# furby_connector_01.net
KiCad netlist of a schematic drawn in EAGLE
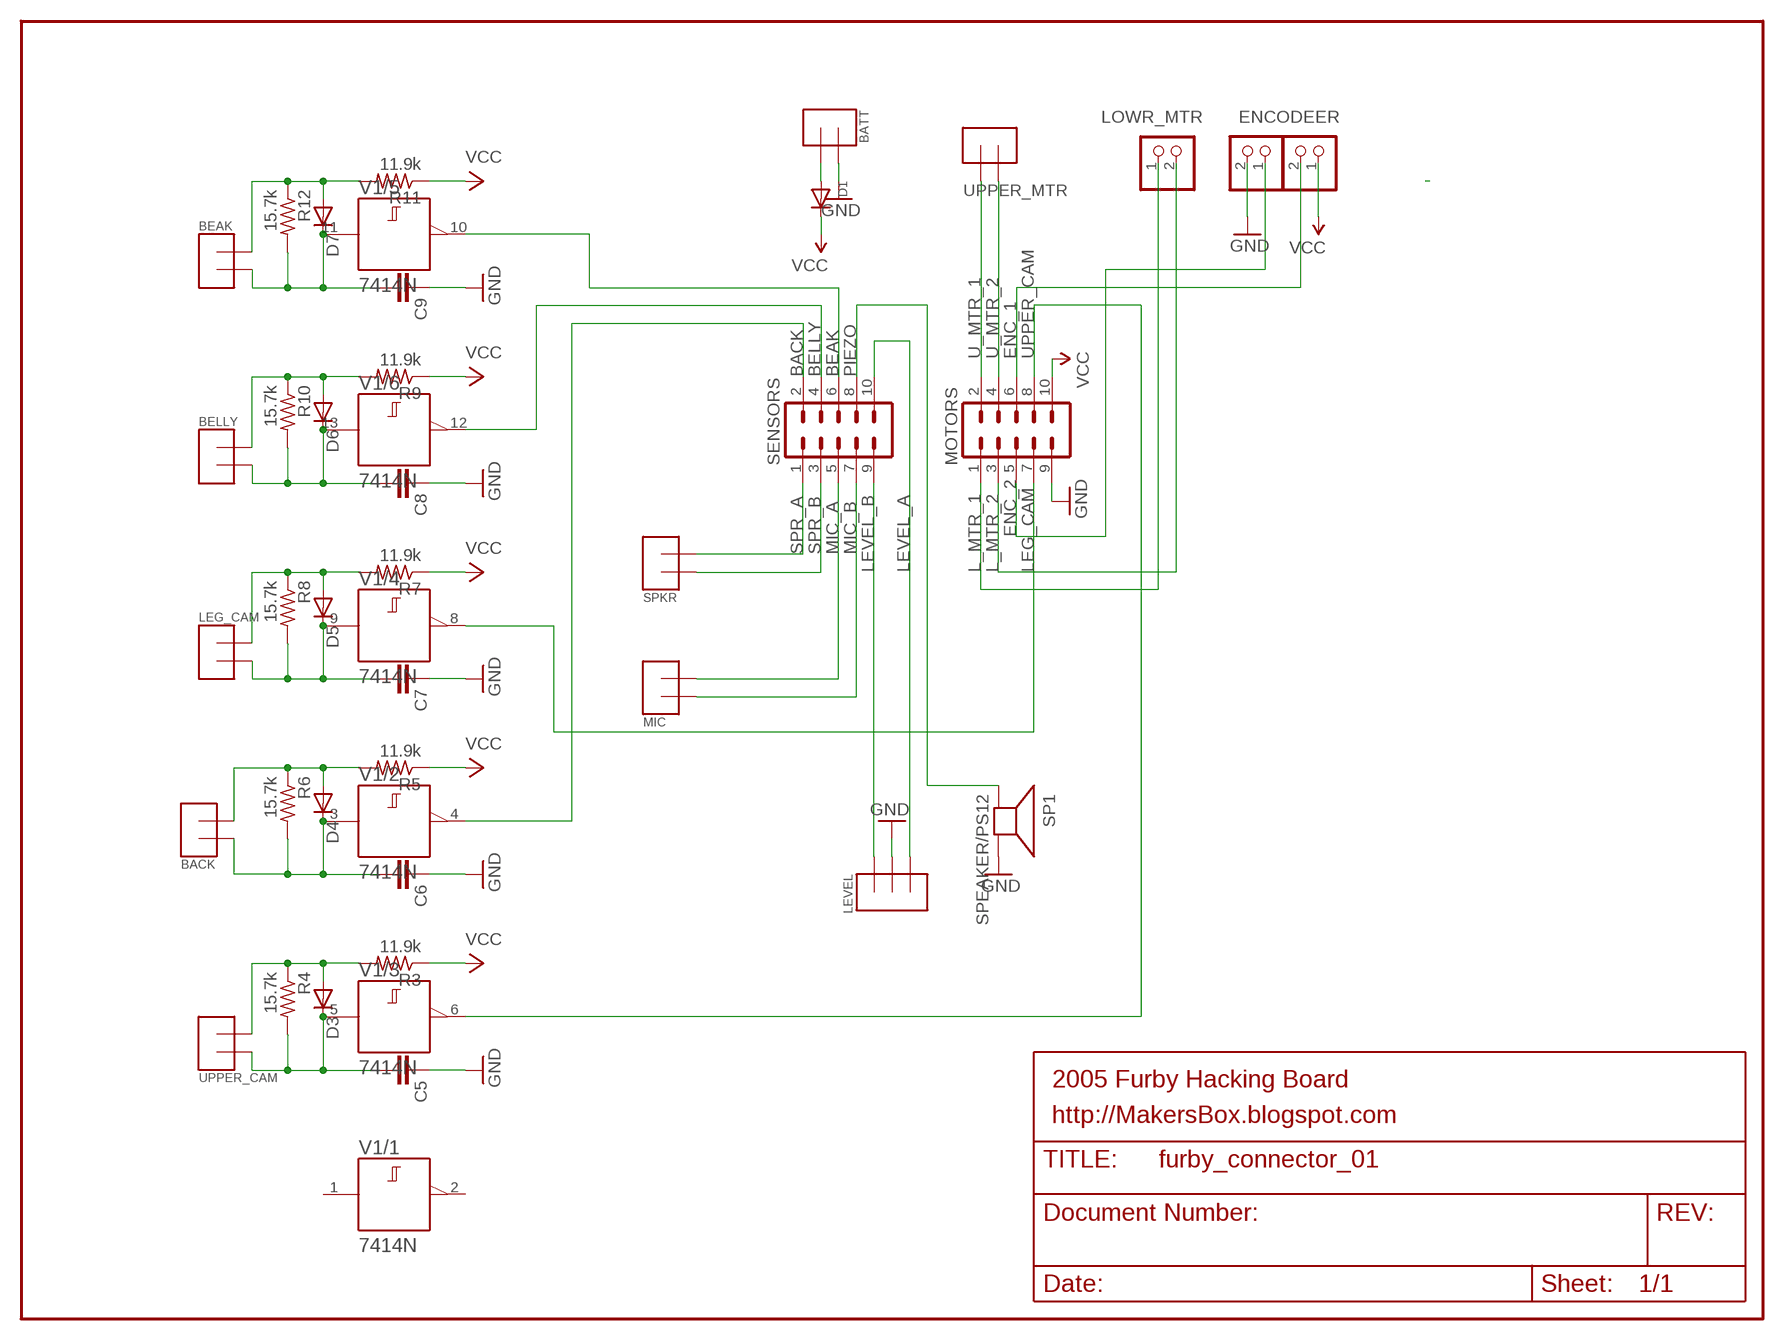
[diagram p0: schematic, sheet 1]

(export (version "E")
  (design (tool "Eeschema 10.0.6"))
  (components
    (comp (ref "BACK")
      (value "TERMINAL2")
      (footprint "eagle-import:TERMINAL_2")
      (libsource (lib "eagle-import") (part "TERMINAL2"))
    )
    (comp (ref "BATT")
      (value "TERMINAL2")
      (footprint "eagle-import:TERMINAL_2")
      (libsource (lib "eagle-import") (part "TERMINAL2"))
    )
    (comp (ref "BEAK")
      (value "TERMINAL2")
      (footprint "eagle-import:TERMINAL_2")
      (libsource (lib "eagle-import") (part "TERMINAL2"))
    )
    (comp (ref "BELLY")
      (value "TERMINAL2")
      (footprint "eagle-import:TERMINAL_2")
      (libsource (lib "eagle-import") (part "TERMINAL2"))
    )
    (comp (ref "C5")
      (value "CAPPTH")
      (footprint "eagle-import:CAP-PTH-SMALL")
      (libsource (lib "eagle-import") (part "CAPPTH"))
    )
    (comp (ref "C6")
      (value "CAPPTH")
      (footprint "eagle-import:CAP-PTH-SMALL")
      (libsource (lib "eagle-import") (part "CAPPTH"))
    )
    (comp (ref "C7")
      (value "CAPPTH")
      (footprint "eagle-import:CAP-PTH-SMALL")
      (libsource (lib "eagle-import") (part "CAPPTH"))
    )
    (comp (ref "C8")
      (value "CAPPTH")
      (footprint "eagle-import:CAP-PTH-SMALL")
      (libsource (lib "eagle-import") (part "CAPPTH"))
    )
    (comp (ref "C9")
      (value "CAPPTH")
      (footprint "eagle-import:CAP-PTH-SMALL")
      (libsource (lib "eagle-import") (part "CAPPTH"))
    )
    (comp (ref "D1")
      (value "DIODEDO-1N4148")
      (footprint "eagle-import:DO-1N4148")
      (libsource (lib "eagle-import") (part "DIODEDO-1N4148"))
    )
    (comp (ref "D3")
      (value "DIODE-D-2.5")
      (footprint "eagle-import:D-2.5")
      (libsource (lib "eagle-import") (part "DIODE-D-2.5"))
    )
    (comp (ref "D4")
      (value "DIODE-D-2.5")
      (footprint "eagle-import:D-2.5")
      (libsource (lib "eagle-import") (part "DIODE-D-2.5"))
    )
    (comp (ref "D5")
      (value "DIODE-D-2.5")
      (footprint "eagle-import:D-2.5")
      (libsource (lib "eagle-import") (part "DIODE-D-2.5"))
    )
    (comp (ref "D6")
      (value "DIODE-D-2.5")
      (footprint "eagle-import:D-2.5")
      (libsource (lib "eagle-import") (part "DIODE-D-2.5"))
    )
    (comp (ref "D7")
      (value "DIODE-D-2.5")
      (footprint "eagle-import:D-2.5")
      (libsource (lib "eagle-import") (part "DIODE-D-2.5"))
    )
    (comp (ref "ENCODE2")
      (value "JST_2PIN-THM")
      (footprint "eagle-import:JST-PH-2-THM")
      (libsource (lib "eagle-import") (part "JST_2PIN-THM"))
    )
    (comp (ref "ENCODEER")
      (value "JST_2PIN-THM")
      (footprint "eagle-import:JST-PH-2-THM")
      (libsource (lib "eagle-import") (part "JST_2PIN-THM"))
    )
    (comp (ref "LEG_CAM")
      (value "TERMINAL2")
      (footprint "eagle-import:TERMINAL_2")
      (libsource (lib "eagle-import") (part "TERMINAL2"))
    )
    (comp (ref "LEVEL")
      (value "TERMINAL")
      (footprint "eagle-import:TERMINAL_3")
      (libsource (lib "eagle-import") (part "TERMINAL"))
    )
    (comp (ref "LOWR_MTR")
      (value "JST_2PIN-THM")
      (footprint "eagle-import:JST-PH-2-THM")
      (libsource (lib "eagle-import") (part "JST_2PIN-THM"))
    )
    (comp (ref "MIC")
      (value "TERMINAL2")
      (footprint "eagle-import:TERMINAL_2")
      (libsource (lib "eagle-import") (part "TERMINAL2"))
    )
    (comp (ref "MOTORS")
      (value "M05X2SHD")
      (footprint "eagle-import:2X5-SHROUDED")
      (libsource (lib "eagle-import") (part "M05X2SHD"))
    )
    (comp (ref "R3")
      (value "11.9k")
      (footprint "eagle-import:0204V")
      (libsource (lib "eagle-import") (part "R-US_0204/2V"))
    )
    (comp (ref "R4")
      (value "15.7k")
      (footprint "eagle-import:0204V")
      (libsource (lib "eagle-import") (part "R-US_0204/2V"))
    )
    (comp (ref "R5")
      (value "11.9k")
      (footprint "eagle-import:0204V")
      (libsource (lib "eagle-import") (part "R-US_0204/2V"))
    )
    (comp (ref "R6")
      (value "15.7k")
      (footprint "eagle-import:0204V")
      (libsource (lib "eagle-import") (part "R-US_0204/2V"))
    )
    (comp (ref "R7")
      (value "11.9k")
      (footprint "eagle-import:0204V")
      (libsource (lib "eagle-import") (part "R-US_0204/2V"))
    )
    (comp (ref "R8")
      (value "15.7k")
      (footprint "eagle-import:0204V")
      (libsource (lib "eagle-import") (part "R-US_0204/2V"))
    )
    (comp (ref "R9")
      (value "11.9k")
      (footprint "eagle-import:0204V")
      (libsource (lib "eagle-import") (part "R-US_0204/2V"))
    )
    (comp (ref "R10")
      (value "15.7k")
      (footprint "eagle-import:0204V")
      (libsource (lib "eagle-import") (part "R-US_0204/2V"))
    )
    (comp (ref "R11")
      (value "11.9k")
      (footprint "eagle-import:0204V")
      (libsource (lib "eagle-import") (part "R-US_0204/2V"))
    )
    (comp (ref "R12")
      (value "15.7k")
      (footprint "eagle-import:0204V")
      (libsource (lib "eagle-import") (part "R-US_0204/2V"))
    )
    (comp (ref "SENSORS")
      (value "M05X2SHD")
      (footprint "eagle-import:2X5-SHROUDED")
      (libsource (lib "eagle-import") (part "M05X2SHD"))
    )
    (comp (ref "SP1")
      (value "SPEAKER/PS12")
      (footprint "eagle-import:PS12")
      (libsource (lib "eagle-import") (part "SPEAKER/PS12"))
    )
    (comp (ref "SPKR")
      (value "TERMINAL2")
      (footprint "eagle-import:TERMINAL_2")
      (libsource (lib "eagle-import") (part "TERMINAL2"))
    )
    (comp (ref "UPPER_CAM")
      (value "TERMINAL2")
      (footprint "eagle-import:TERMINAL_2")
      (libsource (lib "eagle-import") (part "TERMINAL2"))
    )
    (comp (ref "UPPER_MTR")
      (value "TERMINAL2")
      (footprint "eagle-import:TERMINAL_2")
      (libsource (lib "eagle-import") (part "TERMINAL2"))
    )
    (comp (ref "V1")
      (value "7414N")
      (footprint "eagle-import:DIL14")
      (libsource (lib "eagle-import") (part "7414N"))
    )
  )
  (nets
    (net (code "1") (name "/BACK") (class "Default")
      (node (ref "SENSORS") (pin "2") (pinfunction "2_2") (pintype "passive"))
      (node (ref "V1") (pin "4") (pinfunction "Y_4") (pintype "output"))
    )
    (net (code "2") (name "/BEAK") (class "Default")
      (node (ref "SENSORS") (pin "6") (pinfunction "6_6") (pintype "passive"))
      (node (ref "V1") (pin "10") (pinfunction "Y_10") (pintype "output"))
    )
    (net (code "3") (name "/BELLY") (class "Default")
      (node (ref "SENSORS") (pin "4") (pinfunction "4_4") (pintype "passive"))
      (node (ref "V1") (pin "12") (pinfunction "Y_12") (pintype "output"))
    )
    (net (code "4") (name "/ENC_1") (class "Default")
      (node (ref "ENCODE2") (pin "2") (pinfunction "1_2") (pintype "passive"))
      (node (ref "MOTORS") (pin "6") (pinfunction "6_6") (pintype "passive"))
    )
    (net (code "5") (name "/ENC_2") (class "Default")
      (node (ref "ENCODEER") (pin "1") (pinfunction "2_1") (pintype "passive"))
      (node (ref "MOTORS") (pin "5") (pinfunction "5_5") (pintype "passive"))
    )
    (net (code "6") (name "/LEG_CAM") (class "Default")
      (node (ref "MOTORS") (pin "7") (pinfunction "7_7") (pintype "passive"))
      (node (ref "V1") (pin "8") (pinfunction "Y_8") (pintype "output"))
    )
    (net (code "7") (name "/LEVEL_A") (class "Default")
      (node (ref "LEVEL") (pin "P$3") (pinfunction "P$3_P$3") (pintype "bidirectional"))
      (node (ref "SENSORS") (pin "10") (pinfunction "10_10") (pintype "passive"))
    )
    (net (code "8") (name "/LEVEL_B") (class "Default")
      (node (ref "LEVEL") (pin "P$1") (pinfunction "P$1_P$1") (pintype "bidirectional"))
      (node (ref "SENSORS") (pin "9") (pinfunction "9_9") (pintype "passive"))
    )
    (net (code "9") (name "/L_MTR_1") (class "Default")
      (node (ref "LOWR_MTR") (pin "1") (pinfunction "2_1") (pintype "passive"))
      (node (ref "MOTORS") (pin "1") (pinfunction "1_1") (pintype "passive"))
    )
    (net (code "10") (name "/L_MTR_2") (class "Default")
      (node (ref "LOWR_MTR") (pin "2") (pinfunction "1_2") (pintype "passive"))
      (node (ref "MOTORS") (pin "3") (pinfunction "3_3") (pintype "passive"))
    )
    (net (code "11") (name "/MIC_A") (class "Default")
      (node (ref "MIC") (pin "P$2") (pinfunction "P$2_P$2") (pintype "bidirectional"))
      (node (ref "SENSORS") (pin "5") (pinfunction "5_5") (pintype "passive"))
    )
    (net (code "12") (name "/MIC_B") (class "Default")
      (node (ref "MIC") (pin "P$1") (pinfunction "P$1_P$1") (pintype "bidirectional"))
      (node (ref "SENSORS") (pin "7") (pinfunction "7_7") (pintype "passive"))
    )
    (net (code "13") (name "/PIEZO") (class "Default")
      (node (ref "SENSORS") (pin "8") (pinfunction "8_8") (pintype "passive"))
      (node (ref "SP1") (pin "P$1") (pinfunction "+_P$1") (pintype "passive"))
    )
    (net (code "14") (name "/SPR_A") (class "Default")
      (node (ref "SENSORS") (pin "1") (pinfunction "1_1") (pintype "passive"))
      (node (ref "SPKR") (pin "P$2") (pinfunction "P$2_P$2") (pintype "bidirectional"))
    )
    (net (code "15") (name "/SPR_B") (class "Default")
      (node (ref "SENSORS") (pin "3") (pinfunction "3_3") (pintype "passive"))
      (node (ref "SPKR") (pin "P$1") (pinfunction "P$1_P$1") (pintype "bidirectional"))
    )
    (net (code "16") (name "/UPPER_CAM") (class "Default")
      (node (ref "MOTORS") (pin "8") (pinfunction "8_8") (pintype "passive"))
      (node (ref "V1") (pin "6") (pinfunction "Y_6") (pintype "output"))
    )
    (net (code "17") (name "/U_MTR_1") (class "Default")
      (node (ref "MOTORS") (pin "2") (pinfunction "2_2") (pintype "passive"))
      (node (ref "UPPER_MTR") (pin "P$1") (pinfunction "P$1_P$1") (pintype "bidirectional"))
    )
    (net (code "18") (name "/U_MTR_2") (class "Default")
      (node (ref "MOTORS") (pin "4") (pinfunction "4_4") (pintype "passive"))
      (node (ref "UPPER_MTR") (pin "P$2") (pinfunction "P$2_P$2") (pintype "bidirectional"))
    )
    (net (code "19") (name "GND") (class "Default")
      (node (ref "BATT") (pin "P$1") (pinfunction "P$1_P$1") (pintype "bidirectional"))
      (node (ref "C5") (pin "1") (pinfunction "1_1") (pintype "passive"))
      (node (ref "C6") (pin "1") (pinfunction "1_1") (pintype "passive"))
      (node (ref "C7") (pin "1") (pinfunction "1_1") (pintype "passive"))
      (node (ref "C8") (pin "1") (pinfunction "1_1") (pintype "passive"))
      (node (ref "C9") (pin "1") (pinfunction "1_1") (pintype "passive"))
      (node (ref "ENCODEER") (pin "2") (pinfunction "1_2") (pintype "passive"))
      (node (ref "LEVEL") (pin "P$2") (pinfunction "P$2_P$2") (pintype "bidirectional"))
      (node (ref "MOTORS") (pin "9") (pinfunction "9_9") (pintype "passive"))
      (node (ref "SP1") (pin "P$2") (pinfunction "-_P$2") (pintype "passive"))
    )
    (net (code "20") (name "Net-(BACK-PadP$2)") (class "Default")
      (node (ref "BACK") (pin "P$2") (pinfunction "P$2_P$2") (pintype "bidirectional"))
      (node (ref "D4") (pin "A") (pinfunction "A_A") (pintype "passive"))
      (node (ref "R5") (pin "2") (pinfunction "2_2") (pintype "passive"))
      (node (ref "R6") (pin "1") (pinfunction "1_1") (pintype "passive"))
    )
    (net (code "21") (name "Net-(BATT-PadP$2)") (class "Default")
      (node (ref "BATT") (pin "P$2") (pinfunction "P$2_P$2") (pintype "bidirectional"))
      (node (ref "D1") (pin "A") (pinfunction "A_A") (pintype "passive"))
    )
    (net (code "22") (name "Net-(BEAK-PadP$1)") (class "Default")
      (node (ref "BEAK") (pin "P$1") (pinfunction "P$1_P$1") (pintype "bidirectional"))
      (node (ref "D7") (pin "A") (pinfunction "A_A") (pintype "passive"))
      (node (ref "R11") (pin "2") (pinfunction "2_2") (pintype "passive"))
      (node (ref "R12") (pin "1") (pinfunction "1_1") (pintype "passive"))
    )
    (net (code "23") (name "Net-(BELLY-PadP$1)") (class "Default")
      (node (ref "BELLY") (pin "P$1") (pinfunction "P$1_P$1") (pintype "bidirectional"))
      (node (ref "D6") (pin "A") (pinfunction "A_A") (pintype "passive"))
      (node (ref "R10") (pin "1") (pinfunction "1_1") (pintype "passive"))
      (node (ref "R9") (pin "2") (pinfunction "2_2") (pintype "passive"))
    )
    (net (code "24") (name "Net-(D3-PadA)") (class "Default")
      (node (ref "D3") (pin "A") (pinfunction "A_A") (pintype "passive"))
      (node (ref "R3") (pin "2") (pinfunction "2_2") (pintype "passive"))
      (node (ref "R4") (pin "1") (pinfunction "1_1") (pintype "passive"))
      (node (ref "UPPER_CAM") (pin "P$2") (pinfunction "P$2_P$2") (pintype "bidirectional"))
    )
    (net (code "25") (name "Net-(D5-PadA)") (class "Default")
      (node (ref "D5") (pin "A") (pinfunction "A_A") (pintype "passive"))
      (node (ref "LEG_CAM") (pin "P$1") (pinfunction "P$1_P$1") (pintype "bidirectional"))
      (node (ref "R7") (pin "2") (pinfunction "2_2") (pintype "passive"))
      (node (ref "R8") (pin "1") (pinfunction "1_1") (pintype "passive"))
    )
    (net (code "26") (name "Net-(V1D-A)") (class "Default")
      (node (ref "BACK") (pin "P$1") (pinfunction "P$1_P$1") (pintype "bidirectional"))
      (node (ref "C6") (pin "2") (pinfunction "2_2") (pintype "passive"))
      (node (ref "D4") (pin "C") (pinfunction "C_C") (pintype "passive"))
      (node (ref "R6") (pin "2") (pinfunction "2_2") (pintype "passive"))
      (node (ref "V1") (pin "3") (pinfunction "A_3") (pintype "input"))
    )
    (net (code "27") (name "Net-(V1E-A)") (class "Default")
      (node (ref "C5") (pin "2") (pinfunction "2_2") (pintype "passive"))
      (node (ref "D3") (pin "C") (pinfunction "C_C") (pintype "passive"))
      (node (ref "R4") (pin "2") (pinfunction "2_2") (pintype "passive"))
      (node (ref "UPPER_CAM") (pin "P$1") (pinfunction "P$1_P$1") (pintype "bidirectional"))
      (node (ref "V1") (pin "5") (pinfunction "A_5") (pintype "input"))
    )
    (net (code "28") (name "Net-(V1F-A)") (class "Default")
      (node (ref "C7") (pin "2") (pinfunction "2_2") (pintype "passive"))
      (node (ref "D5") (pin "C") (pinfunction "C_C") (pintype "passive"))
      (node (ref "LEG_CAM") (pin "P$2") (pinfunction "P$2_P$2") (pintype "bidirectional"))
      (node (ref "R8") (pin "2") (pinfunction "2_2") (pintype "passive"))
      (node (ref "V1") (pin "9") (pinfunction "A_9") (pintype "input"))
    )
    (net (code "29") (name "Net-(V1G-A)") (class "Default")
      (node (ref "BEAK") (pin "P$2") (pinfunction "P$2_P$2") (pintype "bidirectional"))
      (node (ref "C9") (pin "2") (pinfunction "2_2") (pintype "passive"))
      (node (ref "D7") (pin "C") (pinfunction "C_C") (pintype "passive"))
      (node (ref "R12") (pin "2") (pinfunction "2_2") (pintype "passive"))
      (node (ref "V1") (pin "11") (pinfunction "A_11") (pintype "input"))
    )
    (net (code "30") (name "Net-(V1H-A)") (class "Default")
      (node (ref "BELLY") (pin "P$2") (pinfunction "P$2_P$2") (pintype "bidirectional"))
      (node (ref "C8") (pin "2") (pinfunction "2_2") (pintype "passive"))
      (node (ref "D6") (pin "C") (pinfunction "C_C") (pintype "passive"))
      (node (ref "R10") (pin "2") (pinfunction "2_2") (pintype "passive"))
      (node (ref "V1") (pin "13") (pinfunction "A_13") (pintype "input"))
    )
    (net (code "31") (name "VCC") (class "Default")
      (node (ref "D1") (pin "C") (pinfunction "C_C") (pintype "passive"))
      (node (ref "ENCODE2") (pin "1") (pinfunction "2_1") (pintype "passive"))
      (node (ref "MOTORS") (pin "10") (pinfunction "10_10") (pintype "passive"))
      (node (ref "R11") (pin "1") (pinfunction "1_1") (pintype "passive"))
      (node (ref "R3") (pin "1") (pinfunction "1_1") (pintype "passive"))
      (node (ref "R5") (pin "1") (pinfunction "1_1") (pintype "passive"))
      (node (ref "R7") (pin "1") (pinfunction "1_1") (pintype "passive"))
      (node (ref "R9") (pin "1") (pinfunction "1_1") (pintype "passive"))
    )
    (net (code "32") (name "unconnected-(V1C-A-Pad1)") (class "Default")
      (node (ref "V1") (pin "1") (pinfunction "A_1") (pintype "input"))
    )
    (net (code "33") (name "unconnected-(V1C-Y-Pad2)") (class "Default")
      (node (ref "V1") (pin "2") (pinfunction "Y_2") (pintype "output"))
    )
  )
)
